# BRAIN_Breakout.net
KiCad netlist of a schematic drawn in EAGLE
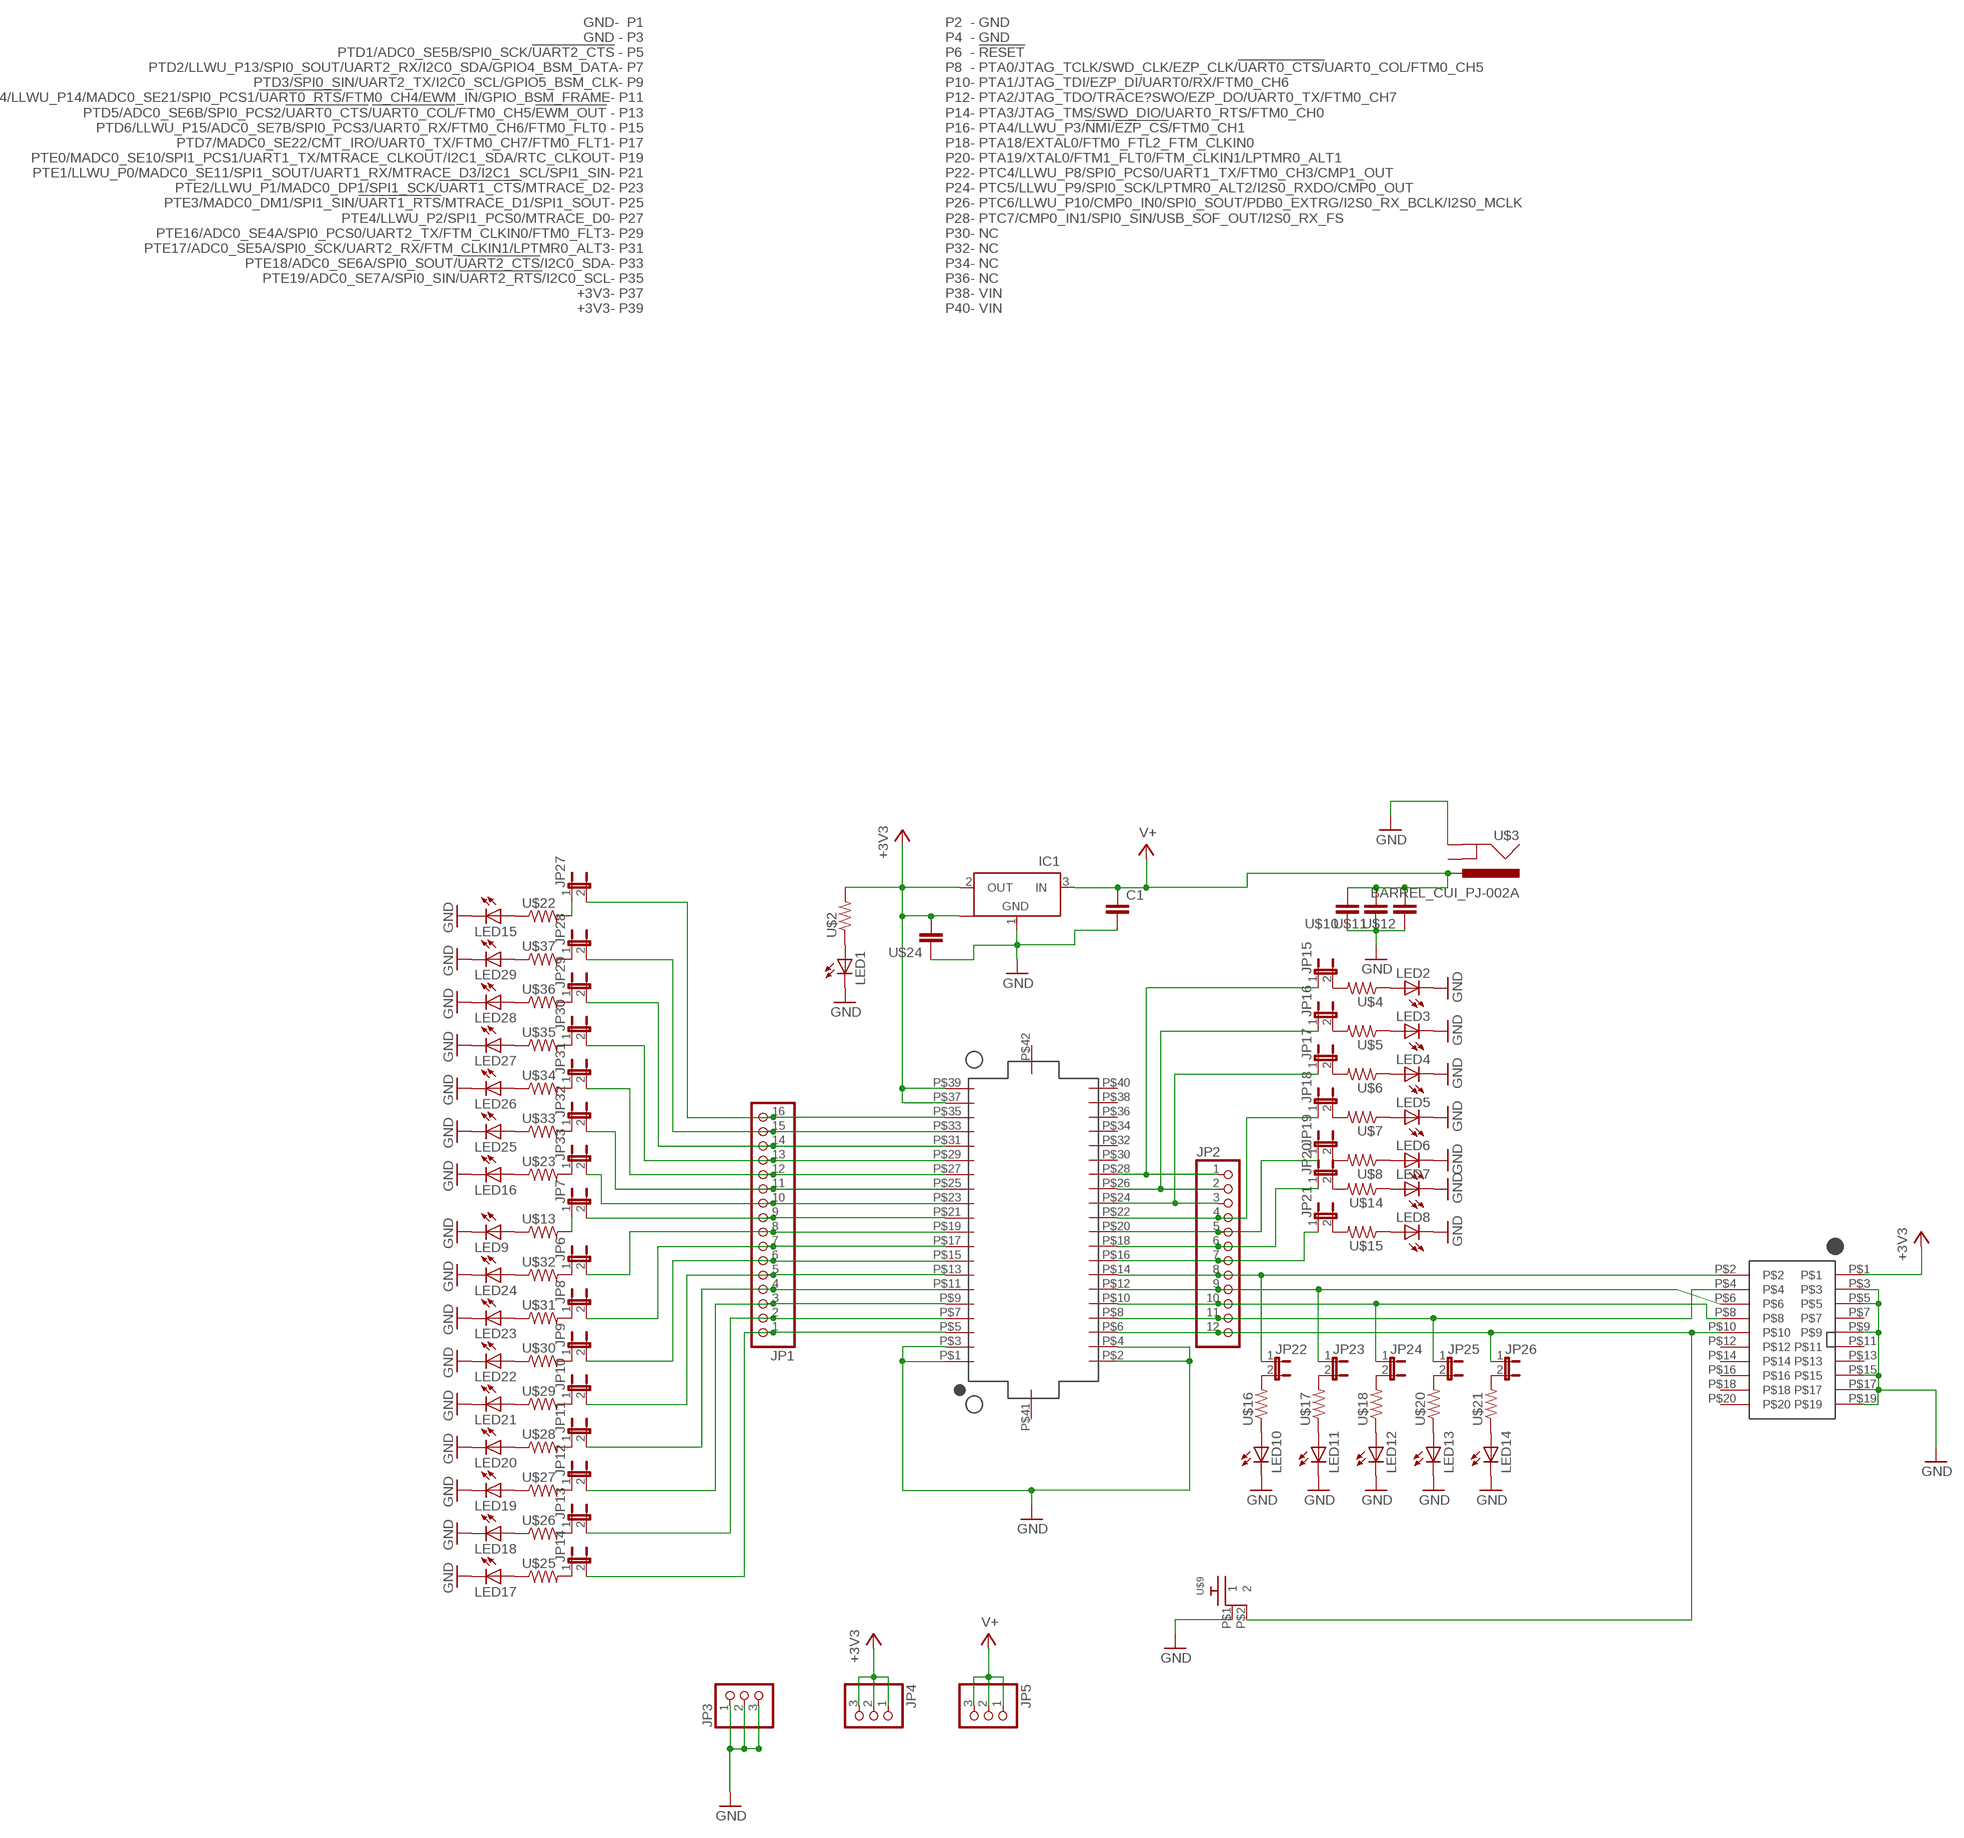
[diagram p0: schematic, sheet 1]

(export (version "E")
  (design (tool "Eeschema 10.0.6"))
  (components
    (comp (ref "C1")
      (value "RF-C0805")
      (footprint "eagle-import:C0805")
      (libsource (lib "eagle-import") (part "RF-C0805"))
    )
    (comp (ref "IC1")
      (value "NCP1117ST33T3G_1")
      (footprint "eagle-import:SOT223")
      (fields (field (name "MFGN") "OnSemi") (field (name "MFGP") "NCP1117ST33T3G"))
      (libsource (lib "eagle-import") (part "NCP1117ST33T3G_1"))
    )
    (comp (ref "JP1")
      (value "PINHD-1X16")
      (footprint "eagle-import:1X16")
      (libsource (lib "eagle-import") (part "PINHD-1X16"))
    )
    (comp (ref "JP2")
      (value "PINHD-1X12")
      (footprint "eagle-import:1X12")
      (libsource (lib "eagle-import") (part "PINHD-1X12"))
    )
    (comp (ref "JP3")
      (value "PINHD-1X3")
      (footprint "eagle-import:1X03")
      (libsource (lib "eagle-import") (part "PINHD-1X3"))
    )
    (comp (ref "JP4")
      (value "PINHD-1X3")
      (footprint "eagle-import:1X03")
      (libsource (lib "eagle-import") (part "PINHD-1X3"))
    )
    (comp (ref "JP5")
      (value "PINHD-1X3")
      (footprint "eagle-import:1X03")
      (libsource (lib "eagle-import") (part "PINHD-1X3"))
    )
    (comp (ref "JP6")
      (value "JUMPER-2SMD-NO-NS")
      (footprint "eagle-import:SJ_2S-NO-NS")
      (libsource (lib "eagle-import") (part "JUMPER-2SMD-NO-NS"))
    )
    (comp (ref "JP7")
      (value "JUMPER-2SMD-NO-NS")
      (footprint "eagle-import:SJ_2S-NO-NS")
      (libsource (lib "eagle-import") (part "JUMPER-2SMD-NO-NS"))
    )
    (comp (ref "JP8")
      (value "JUMPER-2SMD-NO-NS")
      (footprint "eagle-import:SJ_2S-NO-NS")
      (libsource (lib "eagle-import") (part "JUMPER-2SMD-NO-NS"))
    )
    (comp (ref "JP9")
      (value "JUMPER-2SMD-NO-NS")
      (footprint "eagle-import:SJ_2S-NO-NS")
      (libsource (lib "eagle-import") (part "JUMPER-2SMD-NO-NS"))
    )
    (comp (ref "JP10")
      (value "JUMPER-2SMD-NO-NS")
      (footprint "eagle-import:SJ_2S-NO-NS")
      (libsource (lib "eagle-import") (part "JUMPER-2SMD-NO-NS"))
    )
    (comp (ref "JP11")
      (value "JUMPER-2SMD-NO-NS")
      (footprint "eagle-import:SJ_2S-NO-NS")
      (libsource (lib "eagle-import") (part "JUMPER-2SMD-NO-NS"))
    )
    (comp (ref "JP12")
      (value "JUMPER-2SMD-NO-NS")
      (footprint "eagle-import:SJ_2S-NO-NS")
      (libsource (lib "eagle-import") (part "JUMPER-2SMD-NO-NS"))
    )
    (comp (ref "JP13")
      (value "JUMPER-2SMD-NO-NS")
      (footprint "eagle-import:SJ_2S-NO-NS")
      (libsource (lib "eagle-import") (part "JUMPER-2SMD-NO-NS"))
    )
    (comp (ref "JP14")
      (value "JUMPER-2SMD-NO-NS")
      (footprint "eagle-import:SJ_2S-NO-NS")
      (libsource (lib "eagle-import") (part "JUMPER-2SMD-NO-NS"))
    )
    (comp (ref "JP15")
      (value "JUMPER-2SMD-NO-NS")
      (footprint "eagle-import:SJ_2S-NO-NS")
      (libsource (lib "eagle-import") (part "JUMPER-2SMD-NO-NS"))
    )
    (comp (ref "JP16")
      (value "JUMPER-2SMD-NO-NS")
      (footprint "eagle-import:SJ_2S-NO-NS")
      (libsource (lib "eagle-import") (part "JUMPER-2SMD-NO-NS"))
    )
    (comp (ref "JP17")
      (value "JUMPER-2SMD-NO-NS")
      (footprint "eagle-import:SJ_2S-NO-NS")
      (libsource (lib "eagle-import") (part "JUMPER-2SMD-NO-NS"))
    )
    (comp (ref "JP18")
      (value "JUMPER-2SMD-NO-NS")
      (footprint "eagle-import:SJ_2S-NO-NS")
      (libsource (lib "eagle-import") (part "JUMPER-2SMD-NO-NS"))
    )
    (comp (ref "JP19")
      (value "JUMPER-2SMD-NO-NS")
      (footprint "eagle-import:SJ_2S-NO-NS")
      (libsource (lib "eagle-import") (part "JUMPER-2SMD-NO-NS"))
    )
    (comp (ref "JP20")
      (value "JUMPER-2SMD-NO-NS")
      (footprint "eagle-import:SJ_2S-NO-NS")
      (libsource (lib "eagle-import") (part "JUMPER-2SMD-NO-NS"))
    )
    (comp (ref "JP21")
      (value "JUMPER-2SMD-NO-NS")
      (footprint "eagle-import:SJ_2S-NO-NS")
      (libsource (lib "eagle-import") (part "JUMPER-2SMD-NO-NS"))
    )
    (comp (ref "JP22")
      (value "JUMPER-2SMD-NO-NS")
      (footprint "eagle-import:SJ_2S-NO-NS")
      (libsource (lib "eagle-import") (part "JUMPER-2SMD-NO-NS"))
    )
    (comp (ref "JP23")
      (value "JUMPER-2SMD-NO-NS")
      (footprint "eagle-import:SJ_2S-NO-NS")
      (libsource (lib "eagle-import") (part "JUMPER-2SMD-NO-NS"))
    )
    (comp (ref "JP24")
      (value "JUMPER-2SMD-NO-NS")
      (footprint "eagle-import:SJ_2S-NO-NS")
      (libsource (lib "eagle-import") (part "JUMPER-2SMD-NO-NS"))
    )
    (comp (ref "JP25")
      (value "JUMPER-2SMD-NO-NS")
      (footprint "eagle-import:SJ_2S-NO-NS")
      (libsource (lib "eagle-import") (part "JUMPER-2SMD-NO-NS"))
    )
    (comp (ref "JP26")
      (value "JUMPER-2SMD-NO-NS")
      (footprint "eagle-import:SJ_2S-NO-NS")
      (libsource (lib "eagle-import") (part "JUMPER-2SMD-NO-NS"))
    )
    (comp (ref "JP27")
      (value "JUMPER-2SMD-NO-NS")
      (footprint "eagle-import:SJ_2S-NO-NS")
      (libsource (lib "eagle-import") (part "JUMPER-2SMD-NO-NS"))
    )
    (comp (ref "JP28")
      (value "JUMPER-2SMD-NO-NS")
      (footprint "eagle-import:SJ_2S-NO-NS")
      (libsource (lib "eagle-import") (part "JUMPER-2SMD-NO-NS"))
    )
    (comp (ref "JP29")
      (value "JUMPER-2SMD-NO-NS")
      (footprint "eagle-import:SJ_2S-NO-NS")
      (libsource (lib "eagle-import") (part "JUMPER-2SMD-NO-NS"))
    )
    (comp (ref "JP30")
      (value "JUMPER-2SMD-NO-NS")
      (footprint "eagle-import:SJ_2S-NO-NS")
      (libsource (lib "eagle-import") (part "JUMPER-2SMD-NO-NS"))
    )
    (comp (ref "JP31")
      (value "JUMPER-2SMD-NO-NS")
      (footprint "eagle-import:SJ_2S-NO-NS")
      (libsource (lib "eagle-import") (part "JUMPER-2SMD-NO-NS"))
    )
    (comp (ref "JP32")
      (value "JUMPER-2SMD-NO-NS")
      (footprint "eagle-import:SJ_2S-NO-NS")
      (libsource (lib "eagle-import") (part "JUMPER-2SMD-NO-NS"))
    )
    (comp (ref "JP33")
      (value "JUMPER-2SMD-NO-NS")
      (footprint "eagle-import:SJ_2S-NO-NS")
      (libsource (lib "eagle-import") (part "JUMPER-2SMD-NO-NS"))
    )
    (comp (ref "LED1")
      (value "LEDCHIP-LED0805")
      (footprint "eagle-import:CHIP-LED0805")
      (libsource (lib "eagle-import") (part "LEDCHIP-LED0805"))
    )
    (comp (ref "LED2")
      (value "LEDCHIP-LED0805")
      (footprint "eagle-import:CHIP-LED0805")
      (libsource (lib "eagle-import") (part "LEDCHIP-LED0805"))
    )
    (comp (ref "LED3")
      (value "LEDCHIP-LED0805")
      (footprint "eagle-import:CHIP-LED0805")
      (libsource (lib "eagle-import") (part "LEDCHIP-LED0805"))
    )
    (comp (ref "LED4")
      (value "LEDCHIP-LED0805")
      (footprint "eagle-import:CHIP-LED0805")
      (libsource (lib "eagle-import") (part "LEDCHIP-LED0805"))
    )
    (comp (ref "LED5")
      (value "LEDCHIP-LED0805")
      (footprint "eagle-import:CHIP-LED0805")
      (libsource (lib "eagle-import") (part "LEDCHIP-LED0805"))
    )
    (comp (ref "LED6")
      (value "LEDCHIP-LED0805")
      (footprint "eagle-import:CHIP-LED0805")
      (libsource (lib "eagle-import") (part "LEDCHIP-LED0805"))
    )
    (comp (ref "LED7")
      (value "LEDCHIP-LED0805")
      (footprint "eagle-import:CHIP-LED0805")
      (libsource (lib "eagle-import") (part "LEDCHIP-LED0805"))
    )
    (comp (ref "LED8")
      (value "LEDCHIP-LED0805")
      (footprint "eagle-import:CHIP-LED0805")
      (libsource (lib "eagle-import") (part "LEDCHIP-LED0805"))
    )
    (comp (ref "LED9")
      (value "LEDCHIP-LED0805")
      (footprint "eagle-import:CHIP-LED0805")
      (libsource (lib "eagle-import") (part "LEDCHIP-LED0805"))
    )
    (comp (ref "LED10")
      (value "LEDCHIP-LED0805")
      (footprint "eagle-import:CHIP-LED0805")
      (libsource (lib "eagle-import") (part "LEDCHIP-LED0805"))
    )
    (comp (ref "LED11")
      (value "LEDCHIP-LED0805")
      (footprint "eagle-import:CHIP-LED0805")
      (libsource (lib "eagle-import") (part "LEDCHIP-LED0805"))
    )
    (comp (ref "LED12")
      (value "LEDCHIP-LED0805")
      (footprint "eagle-import:CHIP-LED0805")
      (libsource (lib "eagle-import") (part "LEDCHIP-LED0805"))
    )
    (comp (ref "LED13")
      (value "LEDCHIP-LED0805")
      (footprint "eagle-import:CHIP-LED0805")
      (libsource (lib "eagle-import") (part "LEDCHIP-LED0805"))
    )
    (comp (ref "LED14")
      (value "LEDCHIP-LED0805")
      (footprint "eagle-import:CHIP-LED0805")
      (libsource (lib "eagle-import") (part "LEDCHIP-LED0805"))
    )
    (comp (ref "LED15")
      (value "LEDCHIP-LED0805")
      (footprint "eagle-import:CHIP-LED0805")
      (libsource (lib "eagle-import") (part "LEDCHIP-LED0805"))
    )
    (comp (ref "LED16")
      (value "LEDCHIP-LED0805")
      (footprint "eagle-import:CHIP-LED0805")
      (libsource (lib "eagle-import") (part "LEDCHIP-LED0805"))
    )
    (comp (ref "LED17")
      (value "LEDCHIP-LED0805")
      (footprint "eagle-import:CHIP-LED0805")
      (libsource (lib "eagle-import") (part "LEDCHIP-LED0805"))
    )
    (comp (ref "LED18")
      (value "LEDCHIP-LED0805")
      (footprint "eagle-import:CHIP-LED0805")
      (libsource (lib "eagle-import") (part "LEDCHIP-LED0805"))
    )
    (comp (ref "LED19")
      (value "LEDCHIP-LED0805")
      (footprint "eagle-import:CHIP-LED0805")
      (libsource (lib "eagle-import") (part "LEDCHIP-LED0805"))
    )
    (comp (ref "LED20")
      (value "LEDCHIP-LED0805")
      (footprint "eagle-import:CHIP-LED0805")
      (libsource (lib "eagle-import") (part "LEDCHIP-LED0805"))
    )
    (comp (ref "LED21")
      (value "LEDCHIP-LED0805")
      (footprint "eagle-import:CHIP-LED0805")
      (libsource (lib "eagle-import") (part "LEDCHIP-LED0805"))
    )
    (comp (ref "LED22")
      (value "LEDCHIP-LED0805")
      (footprint "eagle-import:CHIP-LED0805")
      (libsource (lib "eagle-import") (part "LEDCHIP-LED0805"))
    )
    (comp (ref "LED23")
      (value "LEDCHIP-LED0805")
      (footprint "eagle-import:CHIP-LED0805")
      (libsource (lib "eagle-import") (part "LEDCHIP-LED0805"))
    )
    (comp (ref "LED24")
      (value "LEDCHIP-LED0805")
      (footprint "eagle-import:CHIP-LED0805")
      (libsource (lib "eagle-import") (part "LEDCHIP-LED0805"))
    )
    (comp (ref "LED25")
      (value "LEDCHIP-LED0805")
      (footprint "eagle-import:CHIP-LED0805")
      (libsource (lib "eagle-import") (part "LEDCHIP-LED0805"))
    )
    (comp (ref "LED26")
      (value "LEDCHIP-LED0805")
      (footprint "eagle-import:CHIP-LED0805")
      (libsource (lib "eagle-import") (part "LEDCHIP-LED0805"))
    )
    (comp (ref "LED27")
      (value "LEDCHIP-LED0805")
      (footprint "eagle-import:CHIP-LED0805")
      (libsource (lib "eagle-import") (part "LEDCHIP-LED0805"))
    )
    (comp (ref "LED28")
      (value "LEDCHIP-LED0805")
      (footprint "eagle-import:CHIP-LED0805")
      (libsource (lib "eagle-import") (part "LEDCHIP-LED0805"))
    )
    (comp (ref "LED29")
      (value "LEDCHIP-LED0805")
      (footprint "eagle-import:CHIP-LED0805")
      (libsource (lib "eagle-import") (part "LEDCHIP-LED0805"))
    )
    (comp (ref "U$1")
      (value "DF12_F")
      (footprint "eagle-import:DF12_F")
      (libsource (lib "eagle-import") (part "DF12_F"))
    )
    (comp (ref "U$2")
      (value "RF-R0805")
      (footprint "eagle-import:RF-C0805")
      (libsource (lib "eagle-import") (part "RF-R0805"))
    )
    (comp (ref "U$3")
      (value "BARREL_CUI_PJ-002A")
      (footprint "eagle-import:BARREL_CUI_PJ-002A")
      (libsource (lib "eagle-import") (part "BARREL_CUI_PJ-002A"))
    )
    (comp (ref "U$4")
      (value "RF-R0805")
      (footprint "eagle-import:RF-C0805")
      (libsource (lib "eagle-import") (part "RF-R0805"))
    )
    (comp (ref "U$5")
      (value "RF-R0805")
      (footprint "eagle-import:RF-C0805")
      (libsource (lib "eagle-import") (part "RF-R0805"))
    )
    (comp (ref "U$6")
      (value "RF-R0805")
      (footprint "eagle-import:RF-C0805")
      (libsource (lib "eagle-import") (part "RF-R0805"))
    )
    (comp (ref "U$7")
      (value "RF-R0805")
      (footprint "eagle-import:RF-C0805")
      (libsource (lib "eagle-import") (part "RF-R0805"))
    )
    (comp (ref "U$8")
      (value "RF-R0805")
      (footprint "eagle-import:RF-C0805")
      (libsource (lib "eagle-import") (part "RF-R0805"))
    )
    (comp (ref "U$9")
      (value "RA_BUTTON")
      (footprint "eagle-import:RA_BUTTON")
      (libsource (lib "eagle-import") (part "RA_BUTTON"))
    )
    (comp (ref "U$10")
      (value "RF-C0805")
      (footprint "eagle-import:C0805")
      (libsource (lib "eagle-import") (part "RF-C0805"))
    )
    (comp (ref "U$11")
      (value "RF-C0805")
      (footprint "eagle-import:C0805")
      (libsource (lib "eagle-import") (part "RF-C0805"))
    )
    (comp (ref "U$12")
      (value "RF-C0805")
      (footprint "eagle-import:C0805")
      (libsource (lib "eagle-import") (part "RF-C0805"))
    )
    (comp (ref "U$13")
      (value "RF-R0805")
      (footprint "eagle-import:RF-C0805")
      (libsource (lib "eagle-import") (part "RF-R0805"))
    )
    (comp (ref "U$14")
      (value "RF-R0805")
      (footprint "eagle-import:RF-C0805")
      (libsource (lib "eagle-import") (part "RF-R0805"))
    )
    (comp (ref "U$15")
      (value "RF-R0805")
      (footprint "eagle-import:RF-C0805")
      (libsource (lib "eagle-import") (part "RF-R0805"))
    )
    (comp (ref "U$16")
      (value "RF-R0805")
      (footprint "eagle-import:RF-C0805")
      (libsource (lib "eagle-import") (part "RF-R0805"))
    )
    (comp (ref "U$17")
      (value "RF-R0805")
      (footprint "eagle-import:RF-C0805")
      (libsource (lib "eagle-import") (part "RF-R0805"))
    )
    (comp (ref "U$18")
      (value "RF-R0805")
      (footprint "eagle-import:RF-C0805")
      (libsource (lib "eagle-import") (part "RF-R0805"))
    )
    (comp (ref "U$19")
      (value "2X10JTAG")
      (footprint "eagle-import:2X10JTAG")
      (libsource (lib "eagle-import") (part "2X10JTAG"))
    )
    (comp (ref "U$20")
      (value "RF-R0805")
      (footprint "eagle-import:RF-C0805")
      (libsource (lib "eagle-import") (part "RF-R0805"))
    )
    (comp (ref "U$21")
      (value "RF-R0805")
      (footprint "eagle-import:RF-C0805")
      (libsource (lib "eagle-import") (part "RF-R0805"))
    )
    (comp (ref "U$22")
      (value "RF-R0805")
      (footprint "eagle-import:RF-C0805")
      (libsource (lib "eagle-import") (part "RF-R0805"))
    )
    (comp (ref "U$23")
      (value "RF-R0805")
      (footprint "eagle-import:RF-C0805")
      (libsource (lib "eagle-import") (part "RF-R0805"))
    )
    (comp (ref "U$24")
      (value "RF-C0805")
      (footprint "eagle-import:C0805")
      (libsource (lib "eagle-import") (part "RF-C0805"))
    )
    (comp (ref "U$25")
      (value "RF-R0805")
      (footprint "eagle-import:RF-C0805")
      (libsource (lib "eagle-import") (part "RF-R0805"))
    )
    (comp (ref "U$26")
      (value "RF-R0805")
      (footprint "eagle-import:RF-C0805")
      (libsource (lib "eagle-import") (part "RF-R0805"))
    )
    (comp (ref "U$27")
      (value "RF-R0805")
      (footprint "eagle-import:RF-C0805")
      (libsource (lib "eagle-import") (part "RF-R0805"))
    )
    (comp (ref "U$28")
      (value "RF-R0805")
      (footprint "eagle-import:RF-C0805")
      (libsource (lib "eagle-import") (part "RF-R0805"))
    )
    (comp (ref "U$29")
      (value "RF-R0805")
      (footprint "eagle-import:RF-C0805")
      (libsource (lib "eagle-import") (part "RF-R0805"))
    )
    (comp (ref "U$30")
      (value "RF-R0805")
      (footprint "eagle-import:RF-C0805")
      (libsource (lib "eagle-import") (part "RF-R0805"))
    )
    (comp (ref "U$31")
      (value "RF-R0805")
      (footprint "eagle-import:RF-C0805")
      (libsource (lib "eagle-import") (part "RF-R0805"))
    )
    (comp (ref "U$32")
      (value "RF-R0805")
      (footprint "eagle-import:RF-C0805")
      (libsource (lib "eagle-import") (part "RF-R0805"))
    )
    (comp (ref "U$33")
      (value "RF-R0805")
      (footprint "eagle-import:RF-C0805")
      (libsource (lib "eagle-import") (part "RF-R0805"))
    )
    (comp (ref "U$34")
      (value "RF-R0805")
      (footprint "eagle-import:RF-C0805")
      (libsource (lib "eagle-import") (part "RF-R0805"))
    )
    (comp (ref "U$35")
      (value "RF-R0805")
      (footprint "eagle-import:RF-C0805")
      (libsource (lib "eagle-import") (part "RF-R0805"))
    )
    (comp (ref "U$36")
      (value "RF-R0805")
      (footprint "eagle-import:RF-C0805")
      (libsource (lib "eagle-import") (part "RF-R0805"))
    )
    (comp (ref "U$37")
      (value "RF-R0805")
      (footprint "eagle-import:RF-C0805")
      (libsource (lib "eagle-import") (part "RF-R0805"))
    )
  )
  (nets
    (net (code "1") (name "+3V3") (class "Default")
      (node (ref "IC1") (pin "2") (pinfunction "OUT_2") (pintype "power_in"))
      (node (ref "IC1") (pin "4") (pinfunction "OUT1_4") (pintype "power_in"))
      (node (ref "JP4") (pin "1") (pinfunction "1_1") (pintype "passive"))
      (node (ref "JP4") (pin "2") (pinfunction "2_2") (pintype "passive"))
      (node (ref "JP4") (pin "3") (pinfunction "3_3") (pintype "passive"))
      (node (ref "U$1") (pin "P$37") (pinfunction "+3V3_P$37") (pintype "bidirectional"))
      (node (ref "U$1") (pin "P$39") (pinfunction "+3V3_P$39") (pintype "bidirectional"))
      (node (ref "U$19") (pin "P$1") (pinfunction "P$1_P$1") (pintype "bidirectional"))
      (node (ref "U$2") (pin "2") (pinfunction "2_2") (pintype "passive"))
      (node (ref "U$24") (pin "2") (pinfunction "2_2") (pintype "passive"))
    )
    (net (code "2") (name "GND") (class "Default")
      (node (ref "C1") (pin "2") (pinfunction "2_2") (pintype "passive"))
      (node (ref "IC1") (pin "1") (pinfunction "GND_1") (pintype "power_in"))
      (node (ref "JP3") (pin "1") (pinfunction "1_1") (pintype "passive"))
      (node (ref "JP3") (pin "2") (pinfunction "2_2") (pintype "passive"))
      (node (ref "JP3") (pin "3") (pinfunction "3_3") (pintype "passive"))
      (node (ref "LED1") (pin "C") (pinfunction "C_C") (pintype "passive"))
      (node (ref "LED10") (pin "C") (pinfunction "C_C") (pintype "passive"))
      (node (ref "LED11") (pin "C") (pinfunction "C_C") (pintype "passive"))
      (node (ref "LED12") (pin "C") (pinfunction "C_C") (pintype "passive"))
      (node (ref "LED13") (pin "C") (pinfunction "C_C") (pintype "passive"))
      (node (ref "LED14") (pin "C") (pinfunction "C_C") (pintype "passive"))
      (node (ref "LED15") (pin "C") (pinfunction "C_C") (pintype "passive"))
      (node (ref "LED16") (pin "C") (pinfunction "C_C") (pintype "passive"))
      (node (ref "LED17") (pin "C") (pinfunction "C_C") (pintype "passive"))
      (node (ref "LED18") (pin "C") (pinfunction "C_C") (pintype "passive"))
      (node (ref "LED19") (pin "C") (pinfunction "C_C") (pintype "passive"))
      (node (ref "LED2") (pin "C") (pinfunction "C_C") (pintype "passive"))
      (node (ref "LED20") (pin "C") (pinfunction "C_C") (pintype "passive"))
      (node (ref "LED21") (pin "C") (pinfunction "C_C") (pintype "passive"))
      (node (ref "LED22") (pin "C") (pinfunction "C_C") (pintype "passive"))
      (node (ref "LED23") (pin "C") (pinfunction "C_C") (pintype "passive"))
      (node (ref "LED24") (pin "C") (pinfunction "C_C") (pintype "passive"))
      (node (ref "LED25") (pin "C") (pinfunction "C_C") (pintype "passive"))
      (node (ref "LED26") (pin "C") (pinfunction "C_C") (pintype "passive"))
      (node (ref "LED27") (pin "C") (pinfunction "C_C") (pintype "passive"))
      (node (ref "LED28") (pin "C") (pinfunction "C_C") (pintype "passive"))
      (node (ref "LED29") (pin "C") (pinfunction "C_C") (pintype "passive"))
      (node (ref "LED3") (pin "C") (pinfunction "C_C") (pintype "passive"))
      (node (ref "LED4") (pin "C") (pinfunction "C_C") (pintype "passive"))
      (node (ref "LED5") (pin "C") (pinfunction "C_C") (pintype "passive"))
      (node (ref "LED6") (pin "C") (pinfunction "C_C") (pintype "passive"))
      (node (ref "LED7") (pin "C") (pinfunction "C_C") (pintype "passive"))
      (node (ref "LED8") (pin "C") (pinfunction "C_C") (pintype "passive"))
      (node (ref "LED9") (pin "C") (pinfunction "C_C") (pintype "passive"))
      (node (ref "U$1") (pin "P$1") (pinfunction "GND_P$1") (pintype "bidirectional"))
      (node (ref "U$1") (pin "P$2") (pinfunction "GND_P$2") (pintype "bidirectional"))
      (node (ref "U$1") (pin "P$3") (pinfunction "GND_P$3") (pintype "bidirectional"))
      (node (ref "U$1") (pin "P$4") (pinfunction "GND_P$4") (pintype "bidirectional"))
      (node (ref "U$10") (pin "1") (pinfunction "1_1") (pintype "passive"))
      (node (ref "U$11") (pin "1") (pinfunction "1_1") (pintype "passive"))
      (node (ref "U$12") (pin "1") (pinfunction "1_1") (pintype "passive"))
      (node (ref "U$19") (pin "P$15") (pinfunction "P$15_P$15") (pintype "bidirectional"))
      (node (ref "U$19") (pin "P$17") (pinfunction "P$17_P$17") (pintype "bidirectional"))
      (node (ref "U$19") (pin "P$19") (pinfunction "P$19_P$19") (pintype "bidirectional"))
      (node (ref "U$19") (pin "P$3") (pinfunction "P$3_P$3") (pintype "bidirectional"))
      (node (ref "U$19") (pin "P$5") (pinfunction "P$5_P$5") (pintype "bidirectional"))
      (node (ref "U$19") (pin "P$9") (pinfunction "P$9_P$9") (pintype "bidirectional"))
      (node (ref "U$24") (pin "1") (pinfunction "1_1") (pintype "passive"))
      (node (ref "U$3") (pin "P$2") (pinfunction "GND_P$2") (pintype "bidirectional"))
      (node (ref "U$9") (pin "P$1") (pinfunction "1_P$1") (pintype "input"))
    )
    (net (code "3") (name "Net-(JP6-Pad1)") (class "Default")
      (node (ref "JP6") (pin "1") (pinfunction "1_1") (pintype "passive"))
      (node (ref "U$32") (pin "2") (pinfunction "2_2") (pintype "passive"))
    )
    (net (code "4") (name "Net-(JP7-Pad1)") (class "Default")
      (node (ref "JP7") (pin "1") (pinfunction "1_1") (pintype "passive"))
      (node (ref "U$13") (pin "2") (pinfunction "2_2") (pintype "passive"))
    )
    (net (code "5") (name "Net-(JP8-Pad1)") (class "Default")
      (node (ref "JP8") (pin "1") (pinfunction "1_1") (pintype "passive"))
      (node (ref "U$31") (pin "2") (pinfunction "2_2") (pintype "passive"))
    )
    (net (code "6") (name "Net-(JP9-Pad1)") (class "Default")
      (node (ref "JP9") (pin "1") (pinfunction "1_1") (pintype "passive"))
      (node (ref "U$30") (pin "2") (pinfunction "2_2") (pintype "passive"))
    )
    (net (code "7") (name "Net-(JP10-Pad1)") (class "Default")
      (node (ref "JP10") (pin "1") (pinfunction "1_1") (pintype "passive"))
      (node (ref "U$29") (pin "2") (pinfunction "2_2") (pintype "passive"))
    )
    (net (code "8") (name "Net-(JP11-Pad1)") (class "Default")
      (node (ref "JP11") (pin "1") (pinfunction "1_1") (pintype "passive"))
      (node (ref "U$28") (pin "2") (pinfunction "2_2") (pintype "passive"))
    )
    (net (code "9") (name "Net-(JP12-Pad1)") (class "Default")
      (node (ref "JP12") (pin "1") (pinfunction "1_1") (pintype "passive"))
      (node (ref "U$27") (pin "2") (pinfunction "2_2") (pintype "passive"))
    )
    (net (code "10") (name "Net-(JP13-Pad1)") (class "Default")
      (node (ref "JP13") (pin "1") (pinfunction "1_1") (pintype "passive"))
      (node (ref "U$26") (pin "2") (pinfunction "2_2") (pintype "passive"))
    )
    (net (code "11") (name "Net-(JP14-Pad1)") (class "Default")
      (node (ref "JP14") (pin "1") (pinfunction "1_1") (pintype "passive"))
      (node (ref "U$25") (pin "2") (pinfunction "2_2") (pintype "passive"))
    )
    (net (code "12") (name "Net-(JP15-Pad2)") (class "Default")
      (node (ref "JP15") (pin "2") (pinfunction "2_2") (pintype "passive"))
      (node (ref "U$4") (pin "2") (pinfunction "2_2") (pintype "passive"))
    )
    (net (code "13") (name "Net-(JP16-Pad2)") (class "Default")
      (node (ref "JP16") (pin "2") (pinfunction "2_2") (pintype "passive"))
      (node (ref "U$5") (pin "2") (pinfunction "2_2") (pintype "passive"))
    )
    (net (code "14") (name "Net-(JP17-Pad2)") (class "Default")
      (node (ref "JP17") (pin "2") (pinfunction "2_2") (pintype "passive"))
      (node (ref "U$6") (pin "2") (pinfunction "2_2") (pintype "passive"))
    )
    (net (code "15") (name "Net-(JP18-Pad2)") (class "Default")
      (node (ref "JP18") (pin "2") (pinfunction "2_2") (pintype "passive"))
      (node (ref "U$7") (pin "2") (pinfunction "2_2") (pintype "passive"))
    )
    (net (code "16") (name "Net-(JP19-Pad2)") (class "Default")
      (node (ref "JP19") (pin "2") (pinfunction "2_2") (pintype "passive"))
      (node (ref "U$8") (pin "2") (pinfunction "2_2") (pintype "passive"))
    )
    (net (code "17") (name "Net-(JP20-Pad2)") (class "Default")
      (node (ref "JP20") (pin "2") (pinfunction "2_2") (pintype "passive"))
      (node (ref "U$14") (pin "2") (pinfunction "2_2") (pintype "passive"))
    )
    (net (code "18") (name "Net-(JP21-Pad2)") (class "Default")
      (node (ref "JP21") (pin "2") (pinfunction "2_2") (pintype "passive"))
      (node (ref "U$15") (pin "2") (pinfunction "2_2") (pintype "passive"))
    )
    (net (code "19") (name "Net-(JP22-Pad2)") (class "Default")
      (node (ref "JP22") (pin "2") (pinfunction "2_2") (pintype "passive"))
      (node (ref "U$16") (pin "2") (pinfunction "2_2") (pintype "passive"))
    )
    (net (code "20") (name "Net-(JP23-Pad2)") (class "Default")
      (node (ref "JP23") (pin "2") (pinfunction "2_2") (pintype "passive"))
      (node (ref "U$17") (pin "2") (pinfunction "2_2") (pintype "passive"))
    )
    (net (code "21") (name "Net-(JP24-Pad2)") (class "Default")
      (node (ref "JP24") (pin "2") (pinfunction "2_2") (pintype "passive"))
      (node (ref "U$18") (pin "2") (pinfunction "2_2") (pintype "passive"))
    )
    (net (code "22") (name "Net-(JP25-Pad2)") (class "Default")
      (node (ref "JP25") (pin "2") (pinfunction "2_2") (pintype "passive"))
      (node (ref "U$20") (pin "2") (pinfunction "2_2") (pintype "passive"))
    )
    (net (code "23") (name "Net-(JP26-Pad2)") (class "Default")
      (node (ref "JP26") (pin "2") (pinfunction "2_2") (pintype "passive"))
      (node (ref "U$21") (pin "2") (pinfunction "2_2") (pintype "passive"))
    )
    (net (code "24") (name "Net-(JP27-Pad1)") (class "Default")
      (node (ref "JP27") (pin "1") (pinfunction "1_1") (pintype "passive"))
      (node (ref "U$22") (pin "2") (pinfunction "2_2") (pintype "passive"))
    )
    (net (code "25") (name "Net-(JP28-Pad1)") (class "Default")
      (node (ref "JP28") (pin "1") (pinfunction "1_1") (pintype "passive"))
      (node (ref "U$37") (pin "2") (pinfunction "2_2") (pintype "passive"))
    )
    (net (code "26") (name "Net-(JP29-Pad1)") (class "Default")
      (node (ref "JP29") (pin "1") (pinfunction "1_1") (pintype "passive"))
      (node (ref "U$36") (pin "2") (pinfunction "2_2") (pintype "passive"))
    )
    (net (code "27") (name "Net-(JP30-Pad1)") (class "Default")
      (node (ref "JP30") (pin "1") (pinfunction "1_1") (pintype "passive"))
      (node (ref "U$35") (pin "2") (pinfunction "2_2") (pintype "passive"))
    )
    (net (code "28") (name "Net-(JP31-Pad1)") (class "Default")
      (node (ref "JP31") (pin "1") (pinfunction "1_1") (pintype "passive"))
      (node (ref "U$34") (pin "2") (pinfunction "2_2") (pintype "passive"))
    )
    (net (code "29") (name "Net-(JP32-Pad1)") (class "Default")
      (node (ref "JP32") (pin "1") (pinfunction "1_1") (pintype "passive"))
      (node (ref "U$33") (pin "2") (pinfunction "2_2") (pintype "passive"))
    )
    (net (code "30") (name "Net-(JP33-Pad1)") (class "Default")
      (node (ref "JP33") (pin "1") (pinfunction "1_1") (pintype "passive"))
      (node (ref "U$23") (pin "2") (pinfunction "2_2") (pintype "passive"))
    )
    (net (code "31") (name "Net-(LED1-PadA)") (class "Default")
      (node (ref "LED1") (pin "A") (pinfunction "A_A") (pintype "passive"))
      (node (ref "U$2") (pin "1") (pinfunction "1_1") (pintype "passive"))
    )
    (net (code "32") (name "Net-(LED2-PadA)") (class "Default")
      (node (ref "LED2") (pin "A") (pinfunction "A_A") (pintype "passive"))
      (node (ref "U$4") (pin "1") (pinfunction "1_1") (pintype "passive"))
    )
    (net (code "33") (name "Net-(LED3-PadA)") (class "Default")
      (node (ref "LED3") (pin "A") (pinfunction "A_A") (pintype "passive"))
      (node (ref "U$5") (pin "1") (pinfunction "1_1") (pintype "passive"))
    )
    (net (code "34") (name "Net-(LED4-PadA)") (class "Default")
      (node (ref "LED4") (pin "A") (pinfunction "A_A") (pintype "passive"))
      (node (ref "U$6") (pin "1") (pinfunction "1_1") (pintype "passive"))
    )
    (net (code "35") (name "Net-(LED5-PadA)") (class "Default")
      (node (ref "LED5") (pin "A") (pinfunction "A_A") (pintype "passive"))
      (node (ref "U$7") (pin "1") (pinfunction "1_1") (pintype "passive"))
    )
    (net (code "36") (name "Net-(LED6-PadA)") (class "Default")
      (node (ref "LED6") (pin "A") (pinfunction "A_A") (pintype "passive"))
      (node (ref "U$8") (pin "1") (pinfunction "1_1") (pintype "passive"))
    )
    (net (code "37") (name "Net-(LED7-PadA)") (class "Default")
      (node (ref "LED7") (pin "A") (pinfunction "A_A") (pintype "passive"))
      (node (ref "U$14") (pin "1") (pinfunction "1_1") (pintype "passive"))
    )
    (net (code "38") (name "Net-(LED8-PadA)") (class "Default")
      (node (ref "LED8") (pin "A") (pinfunction "A_A") (pintype "passive"))
      (node (ref "U$15") (pin "1") (pinfunction "1_1") (pintype "passive"))
    )
    (net (code "39") (name "Net-(LED9-PadA)") (class "Default")
      (node (ref "LED9") (pin "A") (pinfunction "A_A") (pintype "passive"))
      (node (ref "U$13") (pin "1") (pinfunction "1_1") (pintype "passive"))
    )
    (net (code "40") (name "Net-(LED10-PadA)") (class "Default")
      (node (ref "LED10") (pin "A") (pinfunction "A_A") (pintype "passive"))
      (node (ref "U$16") (pin "1") (pinfunction "1_1") (pintype "passive"))
    )
    (net (code "41") (name "Net-(LED11-PadA)") (class "Default")
      (node (ref "LED11") (pin "A") (pinfunction "A_A") (pintype "passive"))
      (node (ref "U$17") (pin "1") (pinfunction "1_1") (pintype "passive"))
    )
    (net (code "42") (name "Net-(LED12-PadA)") (class "Default")
      (node (ref "LED12") (pin "A") (pinfunction "A_A") (pintype "passive"))
      (node (ref "U$18") (pin "1") (pinfunction "1_1") (pintype "passive"))
    )
    (net (code "43") (name "Net-(LED13-PadA)") (class "Default")
      (node (ref "LED13") (pin "A") (pinfunction "A_A") (pintype "passive"))
      (node (ref "U$20") (pin "1") (pinfunction "1_1") (pintype "passive"))
    )
    (net (code "44") (name "Net-(LED14-PadA)") (class "Default")
      (node (ref "LED14") (pin "A") (pinfunction "A_A") (pintype "passive"))
      (node (ref "U$21") (pin "1") (pinfunction "1_1") (pintype "passive"))
    )
    (net (code "45") (name "Net-(LED15-PadA)") (class "Default")
      (node (ref "LED15") (pin "A") (pinfunction "A_A") (pintype "passive"))
      (node (ref "U$22") (pin "1") (pinfunction "1_1") (pintype "passive"))
    )
    (net (code "46") (name "Net-(LED16-PadA)") (class "Default")
      (node (ref "LED16") (pin "A") (pinfunction "A_A") (pintype "passive"))
      (node (ref "U$23") (pin "1") (pinfunction "1_1") (pintype "passive"))
    )
    (net (code "47") (name "Net-(LED17-PadA)") (class "Default")
      (node (ref "LED17") (pin "A") (pinfunction "A_A") (pintype "passive"))
      (node (ref "U$25") (pin "1") (pinfunction "1_1") (pintype "passive"))
    )
    (net (code "48") (name "Net-(LED18-PadA)") (class "Default")
      (node (ref "LED18") (pin "A") (pinfunction "A_A") (pintype "passive"))
      (node (ref "U$26") (pin "1") (pinfunction "1_1") (pintype "passive"))
    )
    (net (code "49") (name "Net-(LED19-PadA)") (class "Default")
      (node (ref "LED19") (pin "A") (pinfunction "A_A") (pintype "passive"))
      (node (ref "U$27") (pin "1") (pinfunction "1_1") (pintype "passive"))
    )
    (net (code "50") (name "Net-(LED20-PadA)") (class "Default")
      (node (ref "LED20") (pin "A") (pinfunction "A_A") (pintype "passive"))
      (node (ref "U$28") (pin "1") (pinfunction "1_1") (pintype "passive"))
    )
    (net (code "51") (name "Net-(LED21-PadA)") (class "Default")
      (node (ref "LED21") (pin "A") (pinfunction "A_A") (pintype "passive"))
      (node (ref "U$29") (pin "1") (pinfunction "1_1") (pintype "passive"))
    )
    (net (code "52") (name "Net-(LED22-PadA)") (class "Default")
      (node (ref "LED22") (pin "A") (pinfunction "A_A") (pintype "passive"))
      (node (ref "U$30") (pin "1") (pinfunction "1_1") (pintype "passive"))
    )
    (net (code "53") (name "Net-(LED23-PadA)") (class "Default")
      (node (ref "LED23") (pin "A") (pinfunction "A_A") (pintype "passive"))
      (node (ref "U$31") (pin "1") (pinfunction "1_1") (pintype "passive"))
    )
    (net (code "54") (name "Net-(LED24-PadA)") (class "Default")
      (node (ref "LED24") (pin "A") (pinfunction "A_A") (pintype "passive"))
      (node (ref "U$32") (pin "1") (pinfunction "1_1") (pintype "passive"))
    )
    (net (code "55") (name "Net-(LED25-PadA)") (class "Default")
      (node (ref "LED25") (pin "A") (pinfunction "A_A") (pintype "passive"))
      (node (ref "U$33") (pin "1") (pinfunction "1_1") (pintype "passive"))
    )
    (net (code "56") (name "Net-(LED26-PadA)") (class "Default")
      (node (ref "LED26") (pin "A") (pinfunction "A_A") (pintype "passive"))
      (node (ref "U$34") (pin "1") (pinfunction "1_1") (pintype "passive"))
    )
    (net (code "57") (name "Net-(LED27-PadA)") (class "Default")
      (node (ref "LED27") (pin "A") (pinfunction "A_A") (pintype "passive"))
      (node (ref "U$35") (pin "1") (pinfunction "1_1") (pintype "passive"))
    )
    (net (code "58") (name "Net-(LED28-PadA)") (class "Default")
      (node (ref "LED28") (pin "A") (pinfunction "A_A") (pintype "passive"))
      (node (ref "U$36") (pin "1") (pinfunction "1_1") (pintype "passive"))
    )
    (net (code "59") (name "Net-(LED29-PadA)") (class "Default")
      (node (ref "LED29") (pin "A") (pinfunction "A_A") (pintype "passive"))
      (node (ref "U$37") (pin "1") (pinfunction "1_1") (pintype "passive"))
    )
    (net (code "60") (name "Net-(U$1-PTA0{slash}JTAG_TCLK{slash}SWD_CLK{slash}EZP_CLK{slash}~{UART0_CTS{slash}}UART0_COL{slash}FTM0_CH5)") (class "Default")
      (node (ref "JP2") (pin "11") (pinfunction "11_11") (pintype "passive"))
      (node (ref "JP25") (pin "1") (pinfunction "1_1") (pintype "passive"))
      (node (ref "U$1") (pin "P$8") (pinfunction "PTA0/JTAG_TCLK/SWD_CLK/EZP_CLK/~{UART0_CTS/}UART0_COL/FTM0_CH5_P$8") (pintype "bidirectional"))
      (node (ref "U$19") (pin "P$4") (pinfunction "P$4_P$4") (pintype "bidirectional"))
    )
    (net (code "61") (name "Net-(U$1-PTA1{slash}JTAG_TDI{slash}EZP_DI{slash}UART0{slash}RX{slash}FTM0_CH6)") (class "Default")
      (node (ref "JP2") (pin "10") (pinfunction "10_10") (pintype "passive"))
      (node (ref "JP24") (pin "1") (pinfunction "1_1") (pintype "passive"))
      (node (ref "U$1") (pin "P$10") (pinfunction "PTA1/JTAG_TDI/EZP_DI/UART0/RX/FTM0_CH6_P$10") (pintype "bidirectional"))
      (node (ref "U$19") (pin "P$8") (pinfunction "P$8_P$8") (pintype "bidirectional"))
    )
    (net (code "62") (name "Net-(U$1-PTA2{slash}JTAG_TDO{slash}TRACE?SWO{slash}EZP_DO{slash}UART0_TX{slash}FTM0_CH7)") (class "Default")
      (node (ref "JP2") (pin "9") (pinfunction "9_9") (pintype "passive"))
      (node (ref "JP23") (pin "1") (pinfunction "1_1") (pintype "passive"))
      (node (ref "U$1") (pin "P$12") (pinfunction "PTA2/JTAG_TDO/TRACE?SWO/EZP_DO/UART0_TX/FTM0_CH7_P$12") (pintype "bidirectional"))
      (node (ref "U$19") (pin "P$6") (pinfunction "P$6_P$6") (pintype "bidirectional"))
    )
    (net (code "63") (name "Net-(U$1-PTA3{slash}JTAG_TMS{slash}SWD_DIO{slash}UART0_RTS{slash}FTM0_CH0)") (class "Default")
      (node (ref "JP2") (pin "8") (pinfunction "8_8") (pintype "passive"))
      (node (ref "JP22") (pin "1") (pinfunction "1_1") (pintype "passive"))
      (node (ref "U$1") (pin "P$14") (pinfunction "PTA3/JTAG_TMS/SWD_DIO/UART0_RTS/FTM0_CH0_P$14") (pintype "bidirectional"))
      (node (ref "U$19") (pin "P$2") (pinfunction "P$2_P$2") (pintype "bidirectional"))
    )
    (net (code "64") (name "Net-(U$1-PTA4{slash}LLWU_P3{slash}~{NMI}{slash}~{EZP_CS}{slash}FTM0_CH1)") (class "Default")
      (node (ref "JP2") (pin "7") (pinfunction "7_7") (pintype "passive"))
      (node (ref "JP21") (pin "1") (pinfunction "1_1") (pintype "passive"))
      (node (ref "U$1") (pin "P$16") (pinfunction "PTA4/LLWU_P3/~{NMI}/~{EZP_CS}/FTM0_CH1_P$16") (pintype "bidirectional"))
    )
    (net (code "65") (name "Net-(U$1-PTA18{slash}EXTAL0{slash}FTM0_FTL2_FTM_CLKIN0)") (class "Default")
      (node (ref "JP2") (pin "6") (pinfunction "6_6") (pintype "passive"))
      (node (ref "JP20") (pin "1") (pinfunction "1_1") (pintype "passive"))
      (node (ref "U$1") (pin "P$18") (pinfunction "PTA18/EXTAL0/FTM0_FTL2_FTM_CLKIN0_P$18") (pintype "bidirectional"))
    )
    (net (code "66") (name "Net-(U$1-PTA19{slash}XTAL0{slash}FTM1_FLT0{slash}FTM_CLKIN1{slash}LPTMR0_ALT1)") (class "Default")
      (node (ref "JP19") (pin "1") (pinfunction "1_1") (pintype "passive"))
      (node (ref "JP2") (pin "5") (pinfunction "5_5") (pintype "passive"))
      (node (ref "U$1") (pin "P$20") (pinfunction "PTA19/XTAL0/FTM1_FLT0/FTM_CLKIN1/LPTMR0_ALT1_P$20") (pintype "bidirectional"))
    )
    (net (code "67") (name "Net-(U$1-PTC4{slash}LLWU_P8{slash}SPI0_PCS0{slash}UART1_TX{slash}FTM0_CH3{slash}CMP1_OUT)") (class "Default")
      (node (ref "JP18") (pin "1") (pinfunction "1_1") (pintype "passive"))
      (node (ref "JP2") (pin "4") (pinfunction "4_4") (pintype "passive"))
      (node (ref "U$1") (pin "P$22") (pinfunction "PTC4/LLWU_P8/SPI0_PCS0/UART1_TX/FTM0_CH3/CMP1_OUT_P$22") (pintype "bidirectional"))
    )
    (net (code "68") (name "Net-(U$1-PTC5{slash}LLWU_P8{slash}SPI0_PCS0{slash}UART1_TX{slash}FTM0_CH3{slash}CMP1_OUT)") (class "Default")
      (node (ref "JP17") (pin "1") (pinfunction "1_1") (pintype "passive"))
      (node (ref "JP2") (pin "3") (pinfunction "3_3") (pintype "passive"))
      (node (ref "U$1") (pin "P$24") (pinfunction "PTC5/LLWU_P8/SPI0_PCS0/UART1_TX/FTM0_CH3/CMP1_OUT_P$24") (pintype "bidirectional"))
    )
    (net (code "69") (name "Net-(U$1-PTC6{slash}LLWU_P10{slash}CMP0_IN0{slash}SPI0_SOUT{slash}PDB0_EXTRG{slash}I2S0_RX_BCLK{slash}I2S0_MCLK)") (class "Default")
      (node (ref "JP16") (pin "1") (pinfunction "1_1") (pintype "passive"))
      (node (ref "JP2") (pin "2") (pinfunction "2_2") (pintype "passive"))
      (node (ref "U$1") (pin "P$26") (pinfunction "PTC6/LLWU_P10/CMP0_IN0/SPI0_SOUT/PDB0_EXTRG/I2S0_RX_BCLK/I2S0_MCLK_P$26") (pintype "bidirectional"))
    )
    (net (code "70") (name "Net-(U$1-PTC7{slash}CMP0_IN1{slash}SPI0_SIN{slash}USB_SOF_OUT{slash}I2S0_RX_FS)") (class "Default")
      (node (ref "JP15") (pin "1") (pinfunction "1_1") (pintype "passive"))
      (node (ref "JP2") (pin "1") (pinfunction "1_1") (pintype "passive"))
      (node (ref "U$1") (pin "P$28") (pinfunction "PTC7/CMP0_IN1/SPI0_SIN/USB_SOF_OUT/I2S0_RX_FS_P$28") (pintype "bidirectional"))
    )
    (net (code "71") (name "Net-(U$1-PTD1{slash}ADC0_SE5B{slash}SPI0_SCK{slash}~{UART2_CTS})") (class "Default")
      (node (ref "JP1") (pin "1") (pinfunction "1_1") (pintype "passive"))
      (node (ref "JP14") (pin "2") (pinfunction "2_2") (pintype "passive"))
      (node (ref "U$1") (pin "P$5") (pinfunction "PTD1/ADC0_SE5B/SPI0_SCK/~{UART2_CTS}_P$5") (pintype "bidirectional"))
    )
    (net (code "72") (name "Net-(U$1-PTD2{slash}LLWU_P13{slash}SPI0_SOUT{slash}UART2_RX{slash}I2C0_SDA{slash}GPIO4_BSM_DATA)") (class "Default")
      (node (ref "JP1") (pin "2") (pinfunction "2_2") (pintype "passive"))
      (node (ref "JP13") (pin "2") (pinfunction "2_2") (pintype "passive"))
      (node (ref "U$1") (pin "P$7") (pinfunction "PTD2/LLWU_P13/SPI0_SOUT/UART2_RX/I2C0_SDA/GPIO4_BSM_DATA_P$7") (pintype "bidirectional"))
    )
    (net (code "73") (name "Net-(U$1-PTD3{slash}SPI0_SIN{slash}UART2_TX{slash}I2C0_SCL{slash}GPIO5_BSM_CLK)") (class "Default")
      (node (ref "JP1") (pin "3") (pinfunction "3_3") (pintype "passive"))
      (node (ref "JP12") (pin "2") (pinfunction "2_2") (pintype "passive"))
      (node (ref "U$1") (pin "P$9") (pinfunction "PTD3/SPI0_SIN/UART2_TX/I2C0_SCL/GPIO5_BSM_CLK_P$9") (pintype "bidirectional"))
    )
    (net (code "74") (name "Net-(U$1-PTD4{slash}LLWU_P14{slash}MADC0_SE21{slash}SPI0_PCS1{slash}~{UART0_RTS}{slash}FTM0_CH4{slash}EWM_IN{slash}GPIO_BSM_FRAME)") (class "Default")
      (node (ref "JP1") (pin "4") (pinfunction "4_4") (pintype "passive"))
      (node (ref "JP11") (pin "2") (pinfunction "2_2") (pintype "passive"))
      (node (ref "U$1") (pin "P$11") (pinfunction "PTD4/LLWU_P14/MADC0_SE21/SPI0_PCS1/~{UART0_RTS}/FTM0_CH4/EWM_IN/GPIO_BSM_FRAME_P$11") (pintype "bidirectional"))
    )
    (net (code "75") (name "Net-(U$1-PTD5{slash}ADC0_SE6B{slash}SPI0_PCS2{slash}~{UART0_CTS}{slash}~{UART0_COL}{slash}FTM0_CH5{slash}~{EWM_OUT})") (class "Default")
      (node (ref "JP1") (pin "5") (pinfunction "5_5") (pintype "passive"))
      (node (ref "JP10") (pin "2") (pinfunction "2_2") (pintype "passive"))
      (node (ref "U$1") (pin "P$13") (pinfunction "PTD5/ADC0_SE6B/SPI0_PCS2/~{UART0_CTS}/~{UART0_COL}/FTM0_CH5/~{EWM_OUT}_P$13") (pintype "bidirectional"))
    )
    (net (code "76") (name "Net-(U$1-PTD6{slash}LLWU_P15{slash}ADC0_SE7B{slash}SPI0_PCS3{slash}UART0_RX{slash}FTM0_CH6{slash}FTM0_FLT0)") (class "Default")
      (node (ref "JP1") (pin "6") (pinfunction "6_6") (pintype "passive"))
      (node (ref "JP9") (pin "2") (pinfunction "2_2") (pintype "passive"))
      (node (ref "U$1") (pin "P$15") (pinfunction "PTD6/LLWU_P15/ADC0_SE7B/SPI0_PCS3/UART0_RX/FTM0_CH6/FTM0_FLT0_P$15") (pintype "bidirectional"))
    )
    (net (code "77") (name "Net-(U$1-PTD7{slash}MADC0_SE22{slash}CMT_IRO{slash}UART0_TX{slash}FTM0_CH7{slash}FTM0_FLT1)") (class "Default")
      (node (ref "JP1") (pin "7") (pinfunction "7_7") (pintype "passive"))
      (node (ref "JP8") (pin "2") (pinfunction "2_2") (pintype "passive"))
      (node (ref "U$1") (pin "P$17") (pinfunction "PTD7/MADC0_SE22/CMT_IRO/UART0_TX/FTM0_CH7/FTM0_FLT1_P$17") (pintype "bidirectional"))
    )
    (net (code "78") (name "Net-(U$1-PTE0{slash}MADC0_SE10{slash}SPI1_PCS1{slash}UART1_TX{slash}MTRACE_CLKOUT{slash}I2C1_SDA{slash}RTC_CLKOUT)") (class "Default")
      (node (ref "JP1") (pin "8") (pinfunction "8_8") (pintype "passive"))
      (node (ref "JP6") (pin "2") (pinfunction "2_2") (pintype "passive"))
      (node (ref "U$1") (pin "P$19") (pinfunction "PTE0/MADC0_SE10/SPI1_PCS1/UART1_TX/MTRACE_CLKOUT/I2C1_SDA/RTC_CLKOUT_P$19") (pintype "bidirectional"))
    )
    (net (code "79") (name "Net-(U$1-PTE1{slash}LLWU_P0{slash}MADC0_SE11{slash}SPI1_SOUT{slash}UART1_RX{slash}MTRACE_D3{slash}I2C1_SCL{slash}SPI1_SIN)") (class "Default")
      (node (ref "JP1") (pin "9") (pinfunction "9_9") (pintype "passive"))
      (node (ref "JP7") (pin "2") (pinfunction "2_2") (pintype "passive"))
      (node (ref "U$1") (pin "P$21") (pinfunction "PTE1/LLWU_P0/MADC0_SE11/SPI1_SOUT/UART1_RX/MTRACE_D3/I2C1_SCL/SPI1_SIN_P$21") (pintype "bidirectional"))
    )
    (net (code "80") (name "Net-(U$1-PTE2{slash}LLWU_P1{slash}MADC0_DP1{slash}SPI1_SCK{slash}~{UART1_CTS}{slash}MTRACE_D2)") (class "Default")
      (node (ref "JP1") (pin "10") (pinfunction "10_10") (pintype "passive"))
      (node (ref "JP33") (pin "2") (pinfunction "2_2") (pintype "passive"))
      (node (ref "U$1") (pin "P$23") (pinfunction "PTE2/LLWU_P1/MADC0_DP1/SPI1_SCK/~{UART1_CTS}/MTRACE_D2_P$23") (pintype "bidirectional"))
    )
    (net (code "81") (name "Net-(U$1-PTE3{slash}MADC0_DM1{slash}SPI1_SIN{slash}~{UART1_RTS}{slash}MTRACE_D1{slash}SPI1_SOUT)") (class "Default")
      (node (ref "JP1") (pin "11") (pinfunction "11_11") (pintype "passive"))
      (node (ref "JP32") (pin "2") (pinfunction "2_2") (pintype "passive"))
      (node (ref "U$1") (pin "P$25") (pinfunction "PTE3/MADC0_DM1/SPI1_SIN/~{UART1_RTS}/MTRACE_D1/SPI1_SOUT_P$25") (pintype "bidirectional"))
    )
    (net (code "82") (name "Net-(U$1-PTE4{slash}LLWU_P2{slash}SPI1_PCS0{slash}MTRACE_D0)") (class "Default")
      (node (ref "JP1") (pin "12") (pinfunction "12_12") (pintype "passive"))
      (node (ref "JP31") (pin "2") (pinfunction "2_2") (pintype "passive"))
      (node (ref "U$1") (pin "P$27") (pinfunction "PTE4/LLWU_P2/SPI1_PCS0/MTRACE_D0_P$27") (pintype "bidirectional"))
    )
    (net (code "83") (name "Net-(U$1-PTE16{slash}ADC0_SE4A{slash}SPI0_PCS0{slash}UART2_TX{slash}FTM_CLKIN0{slash}FTM0_FLT3)") (class "Default")
      (node (ref "JP1") (pin "13") (pinfunction "13_13") (pintype "passive"))
      (node (ref "JP30") (pin "2") (pinfunction "2_2") (pintype "passive"))
      (node (ref "U$1") (pin "P$29") (pinfunction "PTE16/ADC0_SE4A/SPI0_PCS0/UART2_TX/FTM_CLKIN0/FTM0_FLT3_P$29") (pintype "bidirectional"))
    )
    (net (code "84") (name "Net-(U$1-PTE17{slash}ADC0_SE5A{slash}SPI0_SCK{slash}UART2_RX{slash}FTM_CLKIN1{slash}LPTMR0_ALT3)") (class "Default")
      (node (ref "JP1") (pin "14") (pinfunction "14_14") (pintype "passive"))
      (node (ref "JP29") (pin "2") (pinfunction "2_2") (pintype "passive"))
      (node (ref "U$1") (pin "P$31") (pinfunction "PTE17/ADC0_SE5A/SPI0_SCK/UART2_RX/FTM_CLKIN1/LPTMR0_ALT3_P$31") (pintype "bidirectional"))
    )
    (net (code "85") (name "Net-(U$1-PTE18{slash}ADC0_SE6A{slash}SPI0_SOUT{slash}~{UART2_CTS}{slash}I2C0_SDA)") (class "Default")
      (node (ref "JP1") (pin "15") (pinfunction "15_15") (pintype "passive"))
      (node (ref "JP28") (pin "2") (pinfunction "2_2") (pintype "passive"))
      (node (ref "U$1") (pin "P$33") (pinfunction "PTE18/ADC0_SE6A/SPI0_SOUT/~{UART2_CTS}/I2C0_SDA_P$33") (pintype "bidirectional"))
    )
    (net (code "86") (name "Net-(U$1-PTE19{slash}ADC0_SE7A{slash}SPI0_SIN{slash}~{UART2_RTS}{slash}I2C0_SCL)") (class "Default")
      (node (ref "JP1") (pin "16") (pinfunction "16_16") (pintype "passive"))
      (node (ref "JP27") (pin "2") (pinfunction "2_2") (pintype "passive"))
      (node (ref "U$1") (pin "P$35") (pinfunction "PTE19/ADC0_SE7A/SPI0_SIN/~{UART2_RTS}/I2C0_SCL_P$35") (pintype "bidirectional"))
    )
    (net (code "87") (name "Net-(U$1-~{RESET})") (class "Default")
      (node (ref "JP2") (pin "12") (pinfunction "12_12") (pintype "passive"))
      (node (ref "JP26") (pin "1") (pinfunction "1_1") (pintype "passive"))
      (node (ref "U$1") (pin "P$6") (pinfunction "~{RESET}_P$6") (pintype "bidirectional"))
      (node (ref "U$19") (pin "P$10") (pinfunction "P$10_P$10") (pintype "bidirectional"))
      (node (ref "U$9") (pin "P$2") (pinfunction "2_P$2") (pintype "input"))
    )
    (net (code "88") (name "V+") (class "Default")
      (node (ref "C1") (pin "1") (pinfunction "1_1") (pintype "passive"))
      (node (ref "IC1") (pin "3") (pinfunction "IN_3") (pintype "input"))
      (node (ref "JP5") (pin "1") (pinfunction "1_1") (pintype "passive"))
      (node (ref "JP5") (pin "2") (pinfunction "2_2") (pintype "passive"))
      (node (ref "JP5") (pin "3") (pinfunction "3_3") (pintype "passive"))
      (node (ref "U$10") (pin "2") (pinfunction "2_2") (pintype "passive"))
      (node (ref "U$11") (pin "2") (pinfunction "2_2") (pintype "passive"))
      (node (ref "U$12") (pin "2") (pinfunction "2_2") (pintype "passive"))
      (node (ref "U$3") (pin "P$1") (pinfunction "PWR_P$1") (pintype "bidirectional"))
    )
    (net (code "89") (name "unconnected-(U$1-NC-PadP$30)") (class "Default")
      (node (ref "U$1") (pin "P$30") (pinfunction "NC_P$30") (pintype "bidirectional"))
    )
    (net (code "90") (name "unconnected-(U$1-NC-PadP$32)") (class "Default")
      (node (ref "U$1") (pin "P$32") (pinfunction "NC_P$32") (pintype "bidirectional"))
    )
    (net (code "91") (name "unconnected-(U$1-NC-PadP$34)") (class "Default")
      (node (ref "U$1") (pin "P$34") (pinfunction "NC_P$34") (pintype "bidirectional"))
    )
    (net (code "92") (name "unconnected-(U$1-NC-PadP$36)") (class "Default")
      (node (ref "U$1") (pin "P$36") (pinfunction "NC_P$36") (pintype "bidirectional"))
    )
    (net (code "93") (name "unconnected-(U$1-PadP$41)") (class "Default")
      (node (ref "U$1") (pin "P$41") (pinfunction "P$41_P$41") (pintype "bidirectional"))
    )
    (net (code "94") (name "unconnected-(U$1-PadP$42)") (class "Default")
      (node (ref "U$1") (pin "P$42") (pinfunction "P$42_P$42") (pintype "bidirectional"))
    )
    (net (code "95") (name "unconnected-(U$1-VIN-PadP$38)") (class "Default")
      (node (ref "U$1") (pin "P$38") (pinfunction "VIN_P$38") (pintype "bidirectional"))
    )
    (net (code "96") (name "unconnected-(U$1-VIN-PadP$40)") (class "Default")
      (node (ref "U$1") (pin "P$40") (pinfunction "VIN_P$40") (pintype "bidirectional"))
    )
    (net (code "97") (name "unconnected-(U$3-GNDBREAK-PadP$3)") (class "Default")
      (node (ref "U$3") (pin "P$3") (pinfunction "GNDBREAK_P$3") (pintype "bidirectional"))
    )
    (net (code "98") (name "unconnected-(U$19-PadP$7)") (class "Default")
      (node (ref "U$19") (pin "P$7") (pinfunction "P$7_P$7") (pintype "bidirectional"))
    )
    (net (code "99") (name "unconnected-(U$19-PadP$11)") (class "Default")
      (node (ref "U$19") (pin "P$11") (pinfunction "P$11_P$11") (pintype "bidirectional"))
    )
    (net (code "100") (name "unconnected-(U$19-PadP$12)") (class "Default")
      (node (ref "U$19") (pin "P$12") (pinfunction "P$12_P$12") (pintype "bidirectional"))
    )
    (net (code "101") (name "unconnected-(U$19-PadP$13)") (class "Default")
      (node (ref "U$19") (pin "P$13") (pinfunction "P$13_P$13") (pintype "bidirectional"))
    )
    (net (code "102") (name "unconnected-(U$19-PadP$14)") (class "Default")
      (node (ref "U$19") (pin "P$14") (pinfunction "P$14_P$14") (pintype "bidirectional"))
    )
    (net (code "103") (name "unconnected-(U$19-PadP$16)") (class "Default")
      (node (ref "U$19") (pin "P$16") (pinfunction "P$16_P$16") (pintype "bidirectional"))
    )
    (net (code "104") (name "unconnected-(U$19-PadP$18)") (class "Default")
      (node (ref "U$19") (pin "P$18") (pinfunction "P$18_P$18") (pintype "bidirectional"))
    )
    (net (code "105") (name "unconnected-(U$19-PadP$20)") (class "Default")
      (node (ref "U$19") (pin "P$20") (pinfunction "P$20_P$20") (pintype "bidirectional"))
    )
  )
)
